# sensor_PCB.net
KiCad netlist of a schematic drawn in EAGLE
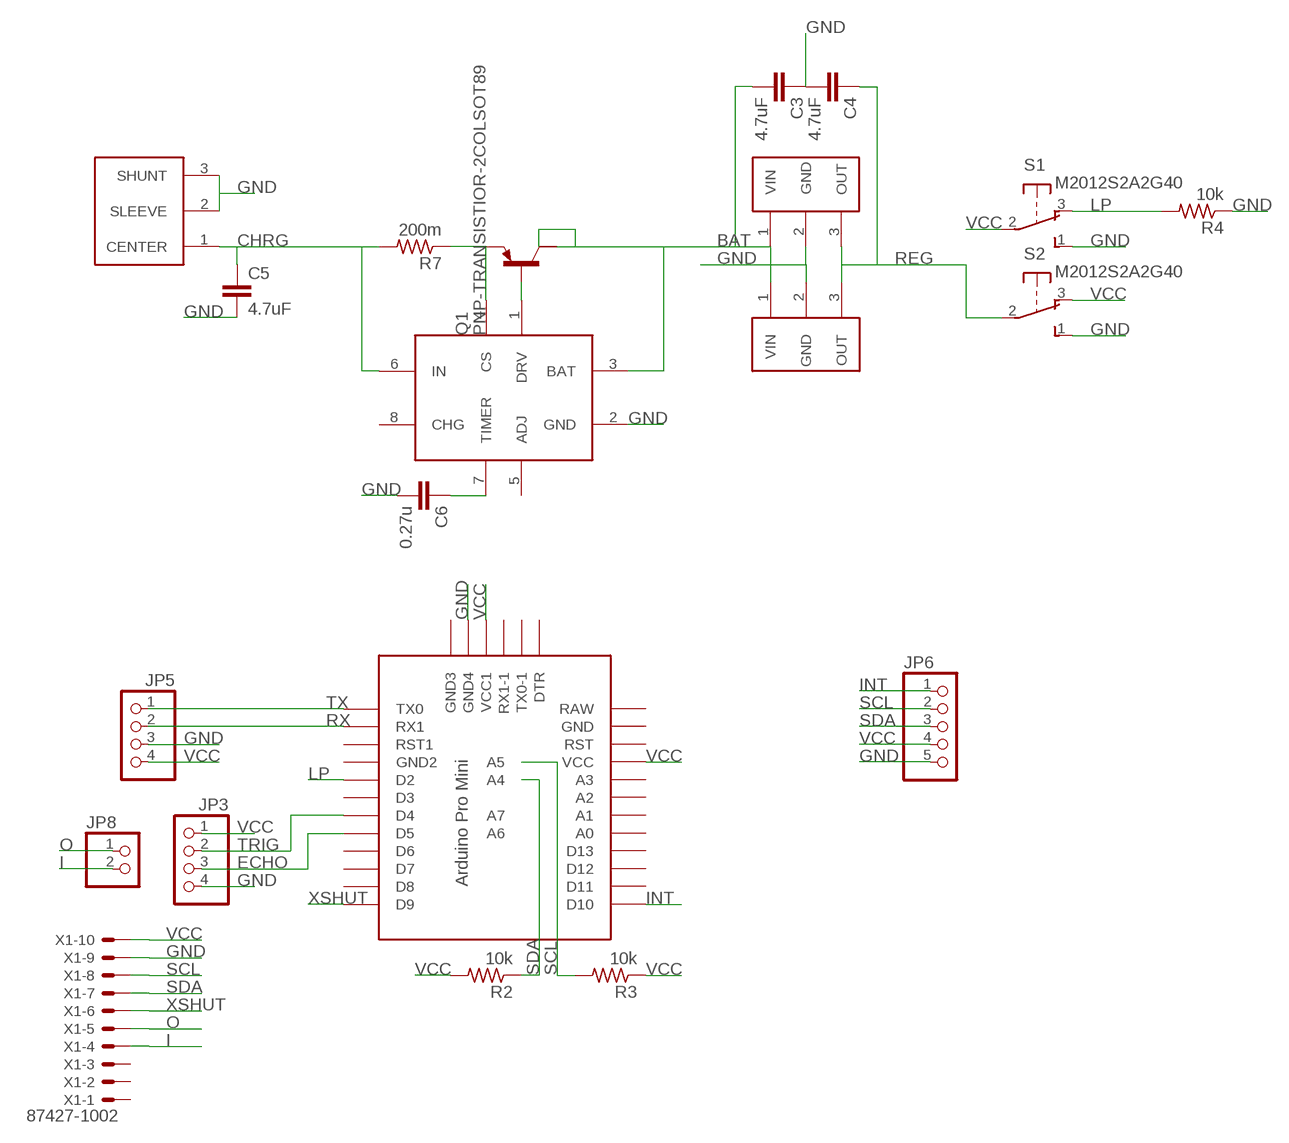
[diagram p0: schematic, sheet 1]

(export (version "E")
  (design (tool "Eeschema 10.0.6"))
  (components
    (comp (ref "C3")
      (value "4.7uF")
      (footprint "eagle-import:0603")
      (libsource (lib "eagle-import") (part "4.7UF0603"))
    )
    (comp (ref "C4")
      (value "4.7uF")
      (footprint "eagle-import:0603")
      (libsource (lib "eagle-import") (part "4.7UF0603"))
    )
    (comp (ref "C5")
      (value "4.7uF")
      (footprint "eagle-import:0603")
      (libsource (lib "eagle-import") (part "4.7UF0603"))
    )
    (comp (ref "C6")
      (value "0.27u")
      (footprint "eagle-import:0805")
      (libsource (lib "eagle-import") (part "0.33UF/330NF-0805-50V-10%"))
    )
    (comp (ref "JP3")
      (value "PINHD-1X4")
      (footprint "eagle-import:1X04")
      (libsource (lib "eagle-import") (part "PINHD-1X4"))
    )
    (comp (ref "JP5")
      (value "PINHD-1X4")
      (footprint "eagle-import:1X04")
      (libsource (lib "eagle-import") (part "PINHD-1X4"))
    )
    (comp (ref "JP6")
      (value "PINHD-1X5")
      (footprint "eagle-import:1X05")
      (libsource (lib "eagle-import") (part "PINHD-1X5"))
    )
    (comp (ref "JP8")
      (value "PINHD-1X2")
      (footprint "eagle-import:1X02")
      (libsource (lib "eagle-import") (part "PINHD-1X2"))
    )
    (comp (ref "Q1")
      (value "PNP-TRANSISTIOR-2COLSOT89")
      (footprint "eagle-import:SOT89")
      (libsource (lib "eagle-import") (part "PNP-TRANSISTIOR-2COLSOT89"))
    )
    (comp (ref "R2")
      (value "10k")
      (footprint "eagle-import:R0603")
      (libsource (lib "eagle-import") (part "R-US_R0603"))
    )
    (comp (ref "R3")
      (value "10k")
      (footprint "eagle-import:R0603")
      (libsource (lib "eagle-import") (part "R-US_R0603"))
    )
    (comp (ref "R4")
      (value "10k")
      (footprint "eagle-import:R0603")
      (libsource (lib "eagle-import") (part "R-US_R0603"))
    )
    (comp (ref "R7")
      (value "200m")
      (footprint "eagle-import:R0603")
      (libsource (lib "eagle-import") (part "R-US_R0603"))
    )
    (comp (ref "S1")
      (value "M2012S2A2G40")
      (footprint "eagle-import:M2012S2A2G40")
      (libsource (lib "eagle-import") (part "M2012S2A2G40"))
    )
    (comp (ref "S2")
      (value "M2012S2A2G40")
      (footprint "eagle-import:M2012S2A2G40")
      (libsource (lib "eagle-import") (part "M2012S2A2G40"))
    )
    (comp (ref "U$1")
      (value "PRO-MINI-2")
      (footprint "eagle-import:PRO-MINI-2")
      (libsource (lib "eagle-import") (part "PRO-MINI-2"))
    )
    (comp (ref "U$3")
      (value "ADP2291")
      (footprint "eagle-import:8-MSOP")
      (libsource (lib "eagle-import") (part "ADP2291"))
    )
    (comp (ref "V3")
      (value "UCC283T-3")
      (footprint "eagle-import:TO220V")
      (libsource (lib "eagle-import") (part "UCC283T-3"))
    )
    (comp (ref "V4")
      (value "UCC283T-3")
      (footprint "eagle-import:TO220V")
      (libsource (lib "eagle-import") (part "UCC283T-3"))
    )
    (comp (ref "V5")
      (value "L712RAS")
      (footprint "eagle-import:L712RAS")
      (libsource (lib "eagle-import") (part "L712RAS"))
    )
    (comp (ref "X1")
      (value "87427-1002")
      (footprint "eagle-import:87427-1002")
      (fields (field (name "MF") "MOLEX"))
      (libsource (lib "eagle-import") (part "87427-1002"))
    )
  )
  (nets
    (net (code "1") (name "/BAT") (class "Default")
      (node (ref "C3") (pin "2") (pinfunction "2_2") (pintype "passive"))
      (node (ref "Q1") (pin "2") (pinfunction "C_2") (pintype "passive"))
      (node (ref "Q1") (pin "2@1") (pinfunction "C/_2@1") (pintype "passive"))
      (node (ref "U$3") (pin "3") (pinfunction "BAT_3") (pintype "bidirectional"))
      (node (ref "V3") (pin "1") (pinfunction "VIN_1") (pintype "bidirectional"))
      (node (ref "V4") (pin "1") (pinfunction "VIN_1") (pintype "bidirectional"))
    )
    (net (code "2") (name "/CHRG") (class "Default")
      (node (ref "C5") (pin "1") (pinfunction "1_1") (pintype "passive"))
      (node (ref "R7") (pin "2") (pinfunction "2_2") (pintype "passive"))
      (node (ref "U$3") (pin "6") (pinfunction "IN_6") (pintype "bidirectional"))
      (node (ref "V5") (pin "1") (pinfunction "CENTER_1") (pintype "bidirectional"))
    )
    (net (code "3") (name "/ECHO") (class "Default")
      (node (ref "JP3") (pin "3") (pinfunction "3_3") (pintype "passive"))
      (node (ref "U$1") (pin "D5") (pinfunction "D5_D5") (pintype "bidirectional"))
    )
    (net (code "4") (name "/GND") (class "Default")
      (node (ref "C3") (pin "1") (pinfunction "1_1") (pintype "passive"))
      (node (ref "C4") (pin "2") (pinfunction "2_2") (pintype "passive"))
      (node (ref "C5") (pin "2") (pinfunction "2_2") (pintype "passive"))
      (node (ref "C6") (pin "2") (pinfunction "2_2") (pintype "passive"))
      (node (ref "JP3") (pin "4") (pinfunction "4_4") (pintype "passive"))
      (node (ref "JP5") (pin "3") (pinfunction "3_3") (pintype "passive"))
      (node (ref "JP6") (pin "5") (pinfunction "5_5") (pintype "passive"))
      (node (ref "R4") (pin "1") (pinfunction "1_1") (pintype "passive"))
      (node (ref "S1") (pin "1") (pinfunction "S_1") (pintype "passive"))
      (node (ref "S2") (pin "1") (pinfunction "S_1") (pintype "passive"))
      (node (ref "U$1") (pin "GND3") (pinfunction "GND4_GND3") (pintype "bidirectional"))
      (node (ref "U$3") (pin "2") (pinfunction "GND_2") (pintype "bidirectional"))
      (node (ref "V3") (pin "2") (pinfunction "GND_2") (pintype "bidirectional"))
      (node (ref "V4") (pin "2") (pinfunction "GND_2") (pintype "bidirectional"))
      (node (ref "V5") (pin "2") (pinfunction "SLEEVE_2") (pintype "bidirectional"))
      (node (ref "V5") (pin "3") (pinfunction "SHUNT_3") (pintype "bidirectional"))
      (node (ref "X1") (pin "9") (pinfunction "S_9") (pintype "passive"))
    )
    (net (code "5") (name "/I") (class "Default")
      (node (ref "JP8") (pin "2") (pinfunction "2_2") (pintype "passive"))
      (node (ref "X1") (pin "4") (pinfunction "S_4") (pintype "passive"))
    )
    (net (code "6") (name "/INT") (class "Default")
      (node (ref "JP6") (pin "1") (pinfunction "1_1") (pintype "passive"))
      (node (ref "U$1") (pin "D10") (pinfunction "D10_D10") (pintype "bidirectional"))
    )
    (net (code "7") (name "/LP") (class "Default")
      (node (ref "R4") (pin "2") (pinfunction "2_2") (pintype "passive"))
      (node (ref "S1") (pin "3") (pinfunction "O_3") (pintype "passive"))
      (node (ref "U$1") (pin "D2") (pinfunction "D2_D2") (pintype "bidirectional"))
    )
    (net (code "8") (name "/O") (class "Default")
      (node (ref "JP8") (pin "1") (pinfunction "1_1") (pintype "passive"))
      (node (ref "X1") (pin "5") (pinfunction "S_5") (pintype "passive"))
    )
    (net (code "9") (name "/REG") (class "Default")
      (node (ref "C4") (pin "1") (pinfunction "1_1") (pintype "passive"))
      (node (ref "S2") (pin "2") (pinfunction "P_2") (pintype "passive"))
      (node (ref "V3") (pin "3") (pinfunction "OUT_3") (pintype "bidirectional"))
      (node (ref "V4") (pin "3") (pinfunction "OUT_3") (pintype "bidirectional"))
    )
    (net (code "10") (name "/RX") (class "Default")
      (node (ref "JP5") (pin "2") (pinfunction "2_2") (pintype "passive"))
      (node (ref "U$1") (pin "RX1") (pinfunction "RX1_RX1") (pintype "bidirectional"))
    )
    (net (code "11") (name "/SCL") (class "Default")
      (node (ref "JP6") (pin "2") (pinfunction "2_2") (pintype "passive"))
      (node (ref "R3") (pin "2") (pinfunction "2_2") (pintype "passive"))
      (node (ref "U$1") (pin "A5") (pinfunction "A5_A5") (pintype "bidirectional"))
      (node (ref "X1") (pin "8") (pinfunction "S_8") (pintype "passive"))
    )
    (net (code "12") (name "/SDA") (class "Default")
      (node (ref "JP6") (pin "3") (pinfunction "3_3") (pintype "passive"))
      (node (ref "R2") (pin "1") (pinfunction "1_1") (pintype "passive"))
      (node (ref "U$1") (pin "A4") (pinfunction "A4_A4") (pintype "bidirectional"))
      (node (ref "X1") (pin "7") (pinfunction "S_7") (pintype "passive"))
    )
    (net (code "13") (name "/TRIG") (class "Default")
      (node (ref "JP3") (pin "2") (pinfunction "2_2") (pintype "passive"))
      (node (ref "U$1") (pin "D4") (pinfunction "D4_D4") (pintype "bidirectional"))
    )
    (net (code "14") (name "/TX") (class "Default")
      (node (ref "JP5") (pin "1") (pinfunction "1_1") (pintype "passive"))
      (node (ref "U$1") (pin "TX0") (pinfunction "TX0_TX0") (pintype "bidirectional"))
    )
    (net (code "15") (name "/VCC") (class "Default")
      (node (ref "JP3") (pin "1") (pinfunction "1_1") (pintype "passive"))
      (node (ref "JP5") (pin "4") (pinfunction "4_4") (pintype "passive"))
      (node (ref "JP6") (pin "4") (pinfunction "4_4") (pintype "passive"))
      (node (ref "R2") (pin "2") (pinfunction "2_2") (pintype "passive"))
      (node (ref "R3") (pin "1") (pinfunction "1_1") (pintype "passive"))
      (node (ref "S1") (pin "2") (pinfunction "P_2") (pintype "passive"))
      (node (ref "S2") (pin "3") (pinfunction "O_3") (pintype "passive"))
      (node (ref "U$1") (pin "VCC") (pinfunction "VCC_VCC") (pintype "bidirectional"))
      (node (ref "U$1") (pin "VCC1") (pinfunction "VCC1_VCC1") (pintype "bidirectional"))
      (node (ref "X1") (pin "10") (pinfunction "S_10") (pintype "passive"))
    )
    (net (code "16") (name "/XSHUT") (class "Default")
      (node (ref "U$1") (pin "D9") (pinfunction "D9_D9") (pintype "bidirectional"))
      (node (ref "X1") (pin "6") (pinfunction "S_6") (pintype "passive"))
    )
    (net (code "17") (name "Net-(Q1-B)") (class "Default")
      (node (ref "Q1") (pin "1") (pinfunction "B_1") (pintype "passive"))
      (node (ref "U$3") (pin "1") (pinfunction "DRV_1") (pintype "bidirectional"))
    )
    (net (code "18") (name "Net-(Q1-E)") (class "Default")
      (node (ref "Q1") (pin "3") (pinfunction "E_3") (pintype "passive"))
      (node (ref "R7") (pin "1") (pinfunction "1_1") (pintype "passive"))
      (node (ref "U$3") (pin "4") (pinfunction "CS_4") (pintype "bidirectional"))
    )
    (net (code "19") (name "Net-(U$3-TIMER)") (class "Default")
      (node (ref "C6") (pin "1") (pinfunction "1_1") (pintype "passive"))
      (node (ref "U$3") (pin "7") (pinfunction "TIMER_7") (pintype "bidirectional"))
    )
    (net (code "20") (name "unconnected-(U$1-GND2-PadGND1)") (class "Default")
      (node (ref "U$1") (pin "GND1") (pinfunction "GND2_GND1") (pintype "bidirectional"))
    )
    (net (code "21") (name "unconnected-(U$1-GND3-PadGND2)") (class "Default")
      (node (ref "U$1") (pin "GND2") (pinfunction "GND3_GND2") (pintype "bidirectional"))
    )
    (net (code "22") (name "unconnected-(U$1-PadA0)") (class "Default")
      (node (ref "U$1") (pin "A0") (pinfunction "A0_A0") (pintype "bidirectional"))
    )
    (net (code "23") (name "unconnected-(U$1-PadA1)") (class "Default")
      (node (ref "U$1") (pin "A1") (pinfunction "A1_A1") (pintype "bidirectional"))
    )
    (net (code "24") (name "unconnected-(U$1-PadA2)") (class "Default")
      (node (ref "U$1") (pin "A2") (pinfunction "A2_A2") (pintype "bidirectional"))
    )
    (net (code "25") (name "unconnected-(U$1-PadA3)") (class "Default")
      (node (ref "U$1") (pin "A3") (pinfunction "A3_A3") (pintype "bidirectional"))
    )
    (net (code "26") (name "unconnected-(U$1-PadA6)") (class "Default")
      (node (ref "U$1") (pin "A6") (pinfunction "A6_A6") (pintype "bidirectional"))
    )
    (net (code "27") (name "unconnected-(U$1-PadA7)") (class "Default")
      (node (ref "U$1") (pin "A7") (pinfunction "A7_A7") (pintype "bidirectional"))
    )
    (net (code "28") (name "unconnected-(U$1-PadD3)") (class "Default")
      (node (ref "U$1") (pin "D3") (pinfunction "D3_D3") (pintype "bidirectional"))
    )
    (net (code "29") (name "unconnected-(U$1-PadD6)") (class "Default")
      (node (ref "U$1") (pin "D6") (pinfunction "D6_D6") (pintype "bidirectional"))
    )
    (net (code "30") (name "unconnected-(U$1-PadD7)") (class "Default")
      (node (ref "U$1") (pin "D7") (pinfunction "D7_D7") (pintype "bidirectional"))
    )
    (net (code "31") (name "unconnected-(U$1-PadD8)") (class "Default")
      (node (ref "U$1") (pin "D8") (pinfunction "D8_D8") (pintype "bidirectional"))
    )
    (net (code "32") (name "unconnected-(U$1-PadD11)") (class "Default")
      (node (ref "U$1") (pin "D11") (pinfunction "D11_D11") (pintype "bidirectional"))
    )
    (net (code "33") (name "unconnected-(U$1-PadD12)") (class "Default")
      (node (ref "U$1") (pin "D12") (pinfunction "D12_D12") (pintype "bidirectional"))
    )
    (net (code "34") (name "unconnected-(U$1-PadD13)") (class "Default")
      (node (ref "U$1") (pin "D13") (pinfunction "D13_D13") (pintype "bidirectional"))
    )
    (net (code "35") (name "unconnected-(U$1-PadDTR)") (class "Default")
      (node (ref "U$1") (pin "DTR") (pinfunction "DTR_DTR") (pintype "bidirectional"))
    )
    (net (code "36") (name "unconnected-(U$1-PadGND)") (class "Default")
      (node (ref "U$1") (pin "GND") (pinfunction "GND_GND") (pintype "bidirectional"))
    )
    (net (code "37") (name "unconnected-(U$1-PadRAW)") (class "Default")
      (node (ref "U$1") (pin "RAW") (pinfunction "RAW_RAW") (pintype "bidirectional"))
    )
    (net (code "38") (name "unconnected-(U$1-PadRST)") (class "Default")
      (node (ref "U$1") (pin "RST") (pinfunction "RST_RST") (pintype "bidirectional"))
    )
    (net (code "39") (name "unconnected-(U$1-PadRST1)") (class "Default")
      (node (ref "U$1") (pin "RST1") (pinfunction "RST1_RST1") (pintype "bidirectional"))
    )
    (net (code "40") (name "unconnected-(U$1-PadRX1-1)") (class "Default")
      (node (ref "U$1") (pin "RX1-1") (pinfunction "RX1-1_RX1-1") (pintype "bidirectional"))
    )
    (net (code "41") (name "unconnected-(U$1-PadTX0-1)") (class "Default")
      (node (ref "U$1") (pin "TX0-1") (pinfunction "TX0-1_TX0-1") (pintype "bidirectional"))
    )
    (net (code "42") (name "unconnected-(U$3-ADJ-Pad5)") (class "Default")
      (node (ref "U$3") (pin "5") (pinfunction "ADJ_5") (pintype "bidirectional"))
    )
    (net (code "43") (name "unconnected-(U$3-CHG-Pad8)") (class "Default")
      (node (ref "U$3") (pin "8") (pinfunction "CHG_8") (pintype "bidirectional"))
    )
    (net (code "44") (name "unconnected-(X1A-S-Pad1)") (class "Default")
      (node (ref "X1") (pin "1") (pinfunction "S_1") (pintype "passive"))
    )
    (net (code "45") (name "unconnected-(X1C-S-Pad2)") (class "Default")
      (node (ref "X1") (pin "2") (pinfunction "S_2") (pintype "passive"))
    )
    (net (code "46") (name "unconnected-(X1D-S-Pad3)") (class "Default")
      (node (ref "X1") (pin "3") (pinfunction "S_3") (pintype "passive"))
    )
  )
)
